# t10_arduino_prog.net
KiCad netlist of a schematic drawn in EAGLE
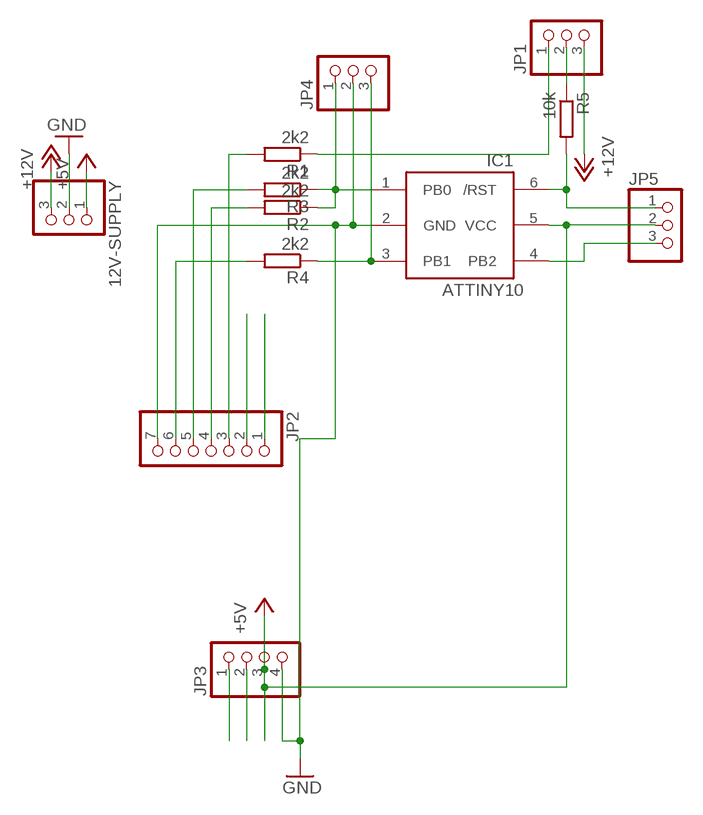
[diagram p0: schematic, sheet 1]

(export (version "E")
  (design (tool "Eeschema 10.0.6"))
  (components
    (comp (ref "12V-SUPPLY")
      (value "PINHD-1X3/90")
      (footprint "eagle-import:1X03_90")
      (libsource (lib "eagle-import") (part "PINHD-1X3/90"))
    )
    (comp (ref "IC1")
      (value "ATTINY10")
      (footprint "eagle-import:SOT23-6")
      (libsource (lib "eagle-import") (part "ATTINY10"))
    )
    (comp (ref "JP1")
      (value "PINHD-1X3")
      (footprint "eagle-import:1X03")
      (libsource (lib "eagle-import") (part "PINHD-1X3"))
    )
    (comp (ref "JP2")
      (value "PINHD-1X7")
      (footprint "eagle-import:1X07")
      (libsource (lib "eagle-import") (part "PINHD-1X7"))
    )
    (comp (ref "JP3")
      (value "PINHD-1X4")
      (footprint "eagle-import:1X04")
      (libsource (lib "eagle-import") (part "PINHD-1X4"))
    )
    (comp (ref "JP4")
      (value "PINHD-1X3")
      (footprint "eagle-import:1X03")
      (libsource (lib "eagle-import") (part "PINHD-1X3"))
    )
    (comp (ref "JP5")
      (value "PINHD-1X3")
      (footprint "eagle-import:1X03")
      (libsource (lib "eagle-import") (part "PINHD-1X3"))
    )
    (comp (ref "R1")
      (value "2k2")
      (footprint "eagle-import:0207_2V")
      (libsource (lib "eagle-import") (part "R-EU_0207/2V"))
    )
    (comp (ref "R2")
      (value "2k2")
      (footprint "eagle-import:0207_2V")
      (libsource (lib "eagle-import") (part "R-EU_0207/2V"))
    )
    (comp (ref "R3")
      (value "2k2")
      (footprint "eagle-import:0207_2V")
      (libsource (lib "eagle-import") (part "R-EU_0207/2V"))
    )
    (comp (ref "R4")
      (value "2k2")
      (footprint "eagle-import:0207_2V")
      (libsource (lib "eagle-import") (part "R-EU_0207/2V"))
    )
    (comp (ref "R5")
      (value "10k")
      (footprint "eagle-import:0207_2V")
      (libsource (lib "eagle-import") (part "R-EU_0207/2V"))
    )
  )
  (nets
    (net (code "1") (name "+5V") (class "Default")
      (node (ref "12V-SUPPLY") (pin "1") (pinfunction "1_1") (pintype "passive"))
      (node (ref "IC1") (pin "5") (pinfunction "VCC_5") (pintype "power_in"))
      (node (ref "JP3") (pin "3") (pinfunction "3_3") (pintype "passive"))
      (node (ref "JP5") (pin "2") (pinfunction "2_2") (pintype "passive"))
    )
    (net (code "2") (name "+12V") (class "Default")
      (node (ref "12V-SUPPLY") (pin "3") (pinfunction "3_3") (pintype "passive"))
      (node (ref "JP1") (pin "3") (pinfunction "3_3") (pintype "passive"))
    )
    (net (code "3") (name "GND") (class "Default")
      (node (ref "12V-SUPPLY") (pin "2") (pinfunction "2_2") (pintype "passive"))
      (node (ref "IC1") (pin "2") (pinfunction "GND_2") (pintype "power_in"))
      (node (ref "JP2") (pin "7") (pinfunction "7_7") (pintype "passive"))
      (node (ref "JP3") (pin "4") (pinfunction "4_4") (pintype "passive"))
      (node (ref "JP4") (pin "2") (pinfunction "2_2") (pintype "passive"))
    )
    (net (code "4") (name "Net-(IC1-PB0)") (class "Default")
      (node (ref "IC1") (pin "1") (pinfunction "PB0_1") (pintype "bidirectional"))
      (node (ref "JP4") (pin "1") (pinfunction "1_1") (pintype "passive"))
      (node (ref "R2") (pin "1") (pinfunction "1_1") (pintype "passive"))
      (node (ref "R3") (pin "1") (pinfunction "1_1") (pintype "passive"))
    )
    (net (code "5") (name "Net-(IC1-PB1)") (class "Default")
      (node (ref "IC1") (pin "3") (pinfunction "PB1_3") (pintype "bidirectional"))
      (node (ref "JP4") (pin "3") (pinfunction "3_3") (pintype "passive"))
      (node (ref "R4") (pin "1") (pinfunction "1_1") (pintype "passive"))
    )
    (net (code "6") (name "Net-(IC1-PB2)") (class "Default")
      (node (ref "IC1") (pin "4") (pinfunction "PB2_4") (pintype "bidirectional"))
      (node (ref "JP5") (pin "3") (pinfunction "3_3") (pintype "passive"))
    )
    (net (code "7") (name "Net-(IC1-{slash}RST)") (class "Default")
      (node (ref "IC1") (pin "6") (pinfunction "/RST_6") (pintype "bidirectional"))
      (node (ref "JP5") (pin "1") (pinfunction "1_1") (pintype "passive"))
      (node (ref "R5") (pin "2") (pinfunction "2_2") (pintype "passive"))
    )
    (net (code "8") (name "Net-(JP1-Pad1)") (class "Default")
      (node (ref "JP1") (pin "1") (pinfunction "1_1") (pintype "passive"))
      (node (ref "R1") (pin "1") (pinfunction "1_1") (pintype "passive"))
    )
    (net (code "9") (name "Net-(JP1-Pad2)") (class "Default")
      (node (ref "JP1") (pin "2") (pinfunction "2_2") (pintype "passive"))
      (node (ref "R5") (pin "1") (pinfunction "1_1") (pintype "passive"))
    )
    (net (code "10") (name "Net-(JP2-Pad3)") (class "Default")
      (node (ref "JP2") (pin "3") (pinfunction "3_3") (pintype "passive"))
      (node (ref "R1") (pin "2") (pinfunction "2_2") (pintype "passive"))
    )
    (net (code "11") (name "Net-(JP2-Pad4)") (class "Default")
      (node (ref "JP2") (pin "4") (pinfunction "4_4") (pintype "passive"))
      (node (ref "R2") (pin "2") (pinfunction "2_2") (pintype "passive"))
    )
    (net (code "12") (name "Net-(JP2-Pad5)") (class "Default")
      (node (ref "JP2") (pin "5") (pinfunction "5_5") (pintype "passive"))
      (node (ref "R3") (pin "2") (pinfunction "2_2") (pintype "passive"))
    )
    (net (code "13") (name "Net-(JP2-Pad6)") (class "Default")
      (node (ref "JP2") (pin "6") (pinfunction "6_6") (pintype "passive"))
      (node (ref "R4") (pin "2") (pinfunction "2_2") (pintype "passive"))
    )
    (net (code "14") (name "unconnected-(JP2-Pad1)") (class "Default")
      (node (ref "JP2") (pin "1") (pinfunction "1_1") (pintype "passive"))
    )
    (net (code "15") (name "unconnected-(JP2-Pad2)") (class "Default")
      (node (ref "JP2") (pin "2") (pinfunction "2_2") (pintype "passive"))
    )
    (net (code "16") (name "unconnected-(JP3-Pad1)") (class "Default")
      (node (ref "JP3") (pin "1") (pinfunction "1_1") (pintype "passive"))
    )
    (net (code "17") (name "unconnected-(JP3-Pad2)") (class "Default")
      (node (ref "JP3") (pin "2") (pinfunction "2_2") (pintype "passive"))
    )
  )
)
